# Input_channel.net
KiCad netlist of a schematic drawn in Altium Designer
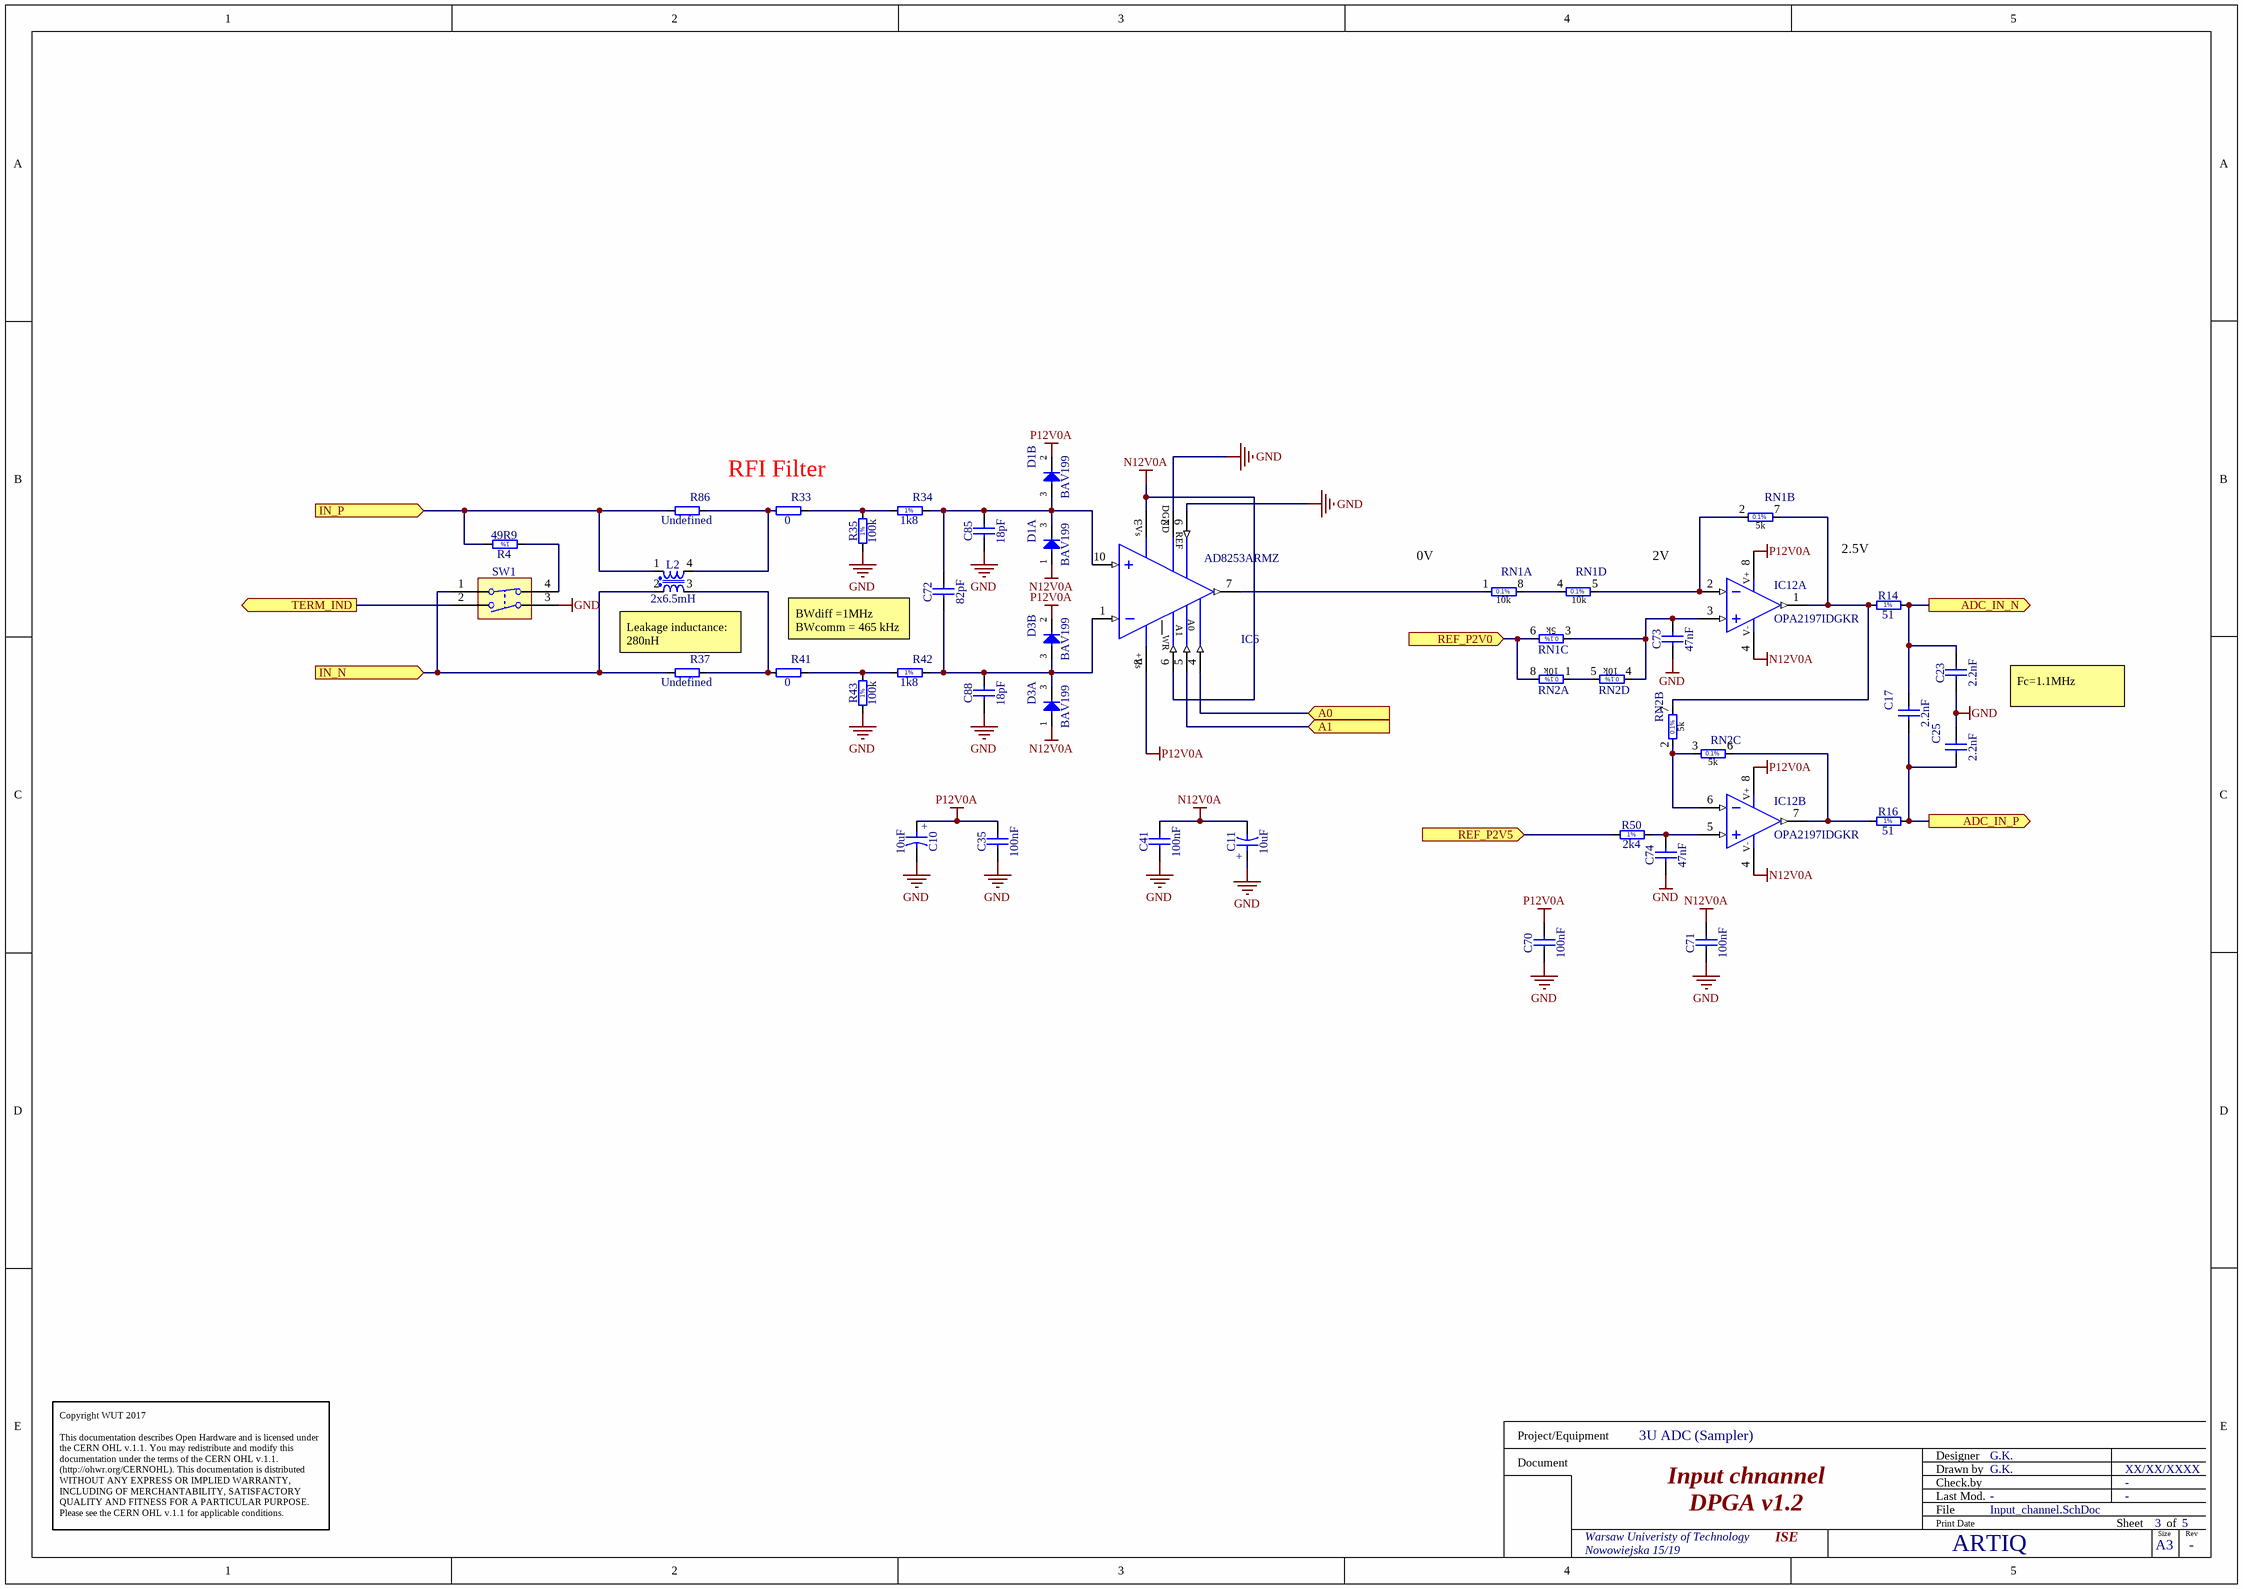
[diagram p0: Input_channel.SchDoc]

(export (version "E")
  (design (tool "Eeschema 10.0.6"))
  (components
    (comp (ref "C10")
      (value "10uF")
      (footprint "CAPMP3216X180N")
      (description "Polarised capacitor")
      (fields
        (field (name "PART NUMBER") "CTE3216-18_10UF_16V_20%_AVX_TCJ")
        (field (name "VOLTAGE") "16V")
        (field (name "AUTHOR") "CERN DEM JLC")
      )
      (libsource (lib "Capacitors") (part "Capacitor - polarized"))
    )
    (comp (ref "C11")
      (value "10uF")
      (footprint "CAPMP3216X180N")
      (description "Polarised capacitor")
      (fields
        (field (name "PART NUMBER") "CTE3216-18_10UF_16V_20%_AVX_TCJ")
        (field (name "VOLTAGE") "16V")
        (field (name "AUTHOR") "CERN DEM JLC")
      )
      (libsource (lib "Capacitors") (part "Capacitor - polarized"))
    )
    (comp (ref "C17")
      (value "2.2nF")
      (footprint "CAPC2013X100N")
      (description "Non-polarised capacitor")
      (fields
        (field (name "PART NUMBER") "CC0805_2.2NF_25V_1%_C0G")
        (field (name "VOLTAGE") "25V")
        (field (name "AUTHOR") "CERN DEM JLC")
      )
      (libsource (lib "Capacitors") (part "Capacitor - non polarized"))
    )
    (comp (ref "C23")
      (value "2.2nF")
      (footprint "CAPC2013X100N")
      (description "Non-polarised capacitor")
      (fields
        (field (name "PART NUMBER") "CC0805_2.2NF_25V_1%_C0G")
        (field (name "VOLTAGE") "25V")
        (field (name "AUTHOR") "CERN DEM JLC")
      )
      (libsource (lib "Capacitors") (part "Capacitor - non polarized"))
    )
    (comp (ref "C25")
      (value "2.2nF")
      (footprint "CAPC2013X100N")
      (description "Non-polarised capacitor")
      (fields
        (field (name "PART NUMBER") "CC0805_2.2NF_25V_1%_C0G")
        (field (name "VOLTAGE") "25V")
        (field (name "AUTHOR") "CERN DEM JLC")
      )
      (libsource (lib "Capacitors") (part "Capacitor - non polarized"))
    )
    (comp (ref "C35")
      (value "100nF")
      (footprint "CAPC1005X55N")
      (description "Non-polarised capacitor")
      (fields
        (field (name "PART NUMBER") "CC0402_100NF_16V_10%_X7R")
        (field (name "VOLTAGE") "16V")
        (field (name "AUTHOR") "CERN DEM JLC")
      )
      (libsource (lib "Capacitors") (part "Capacitor - non polarized"))
    )
    (comp (ref "C41")
      (value "100nF")
      (footprint "CAPC1005X55N")
      (description "Non-polarised capacitor")
      (fields
        (field (name "PART NUMBER") "CC0402_100NF_16V_10%_X7R")
        (field (name "VOLTAGE") "16V")
        (field (name "AUTHOR") "CERN DEM JLC")
      )
      (libsource (lib "Capacitors") (part "Capacitor - non polarized"))
    )
    (comp (ref "C70")
      (value "100nF")
      (footprint "CAPC1005X55N")
      (description "Non-polarised capacitor")
      (fields
        (field (name "PART NUMBER") "CC0402_100NF_16V_10%_X7R")
        (field (name "VOLTAGE") "16V")
        (field (name "AUTHOR") "CERN DEM JLC")
      )
      (libsource (lib "Capacitors") (part "Capacitor - non polarized"))
    )
    (comp (ref "C71")
      (value "100nF")
      (footprint "CAPC1005X55N")
      (description "Non-polarised capacitor")
      (fields
        (field (name "PART NUMBER") "CC0402_100NF_16V_10%_X7R")
        (field (name "VOLTAGE") "16V")
        (field (name "AUTHOR") "CERN DEM JLC")
      )
      (libsource (lib "Capacitors") (part "Capacitor - non polarized"))
    )
    (comp (ref "C72")
      (value "82pF")
      (footprint "CAPC2012X90N")
      (description "Non-polarised capacitor")
      (fields
        (field (name "PART NUMBER") "CC0805_82PF_100V_1%_NP0_AVX_08051A820FAT2A")
        (field (name "VOLTAGE") "100V")
        (field (name "AUTHOR") "CERN DEM WB")
      )
      (libsource (lib "Capacitors") (part "Capacitor - non polarized"))
    )
    (comp (ref "C73")
      (value "47nF")
      (footprint "CAPC2012X135N")
      (description "Non-polarised capacitor")
      (fields
        (field (name "PART NUMBER") "CC0805_47NF_25V_5%_C0G")
        (field (name "VOLTAGE") "25V")
        (field (name "AUTHOR") "CERN DEM JLC")
      )
      (libsource (lib "Capacitors") (part "Capacitor - non polarized"))
    )
    (comp (ref "C74")
      (value "47nF")
      (footprint "CAPC2012X135N")
      (description "Non-polarised capacitor")
      (fields
        (field (name "PART NUMBER") "CC0805_47NF_25V_5%_C0G")
        (field (name "VOLTAGE") "25V")
        (field (name "AUTHOR") "CERN DEM JLC")
      )
      (libsource (lib "Capacitors") (part "Capacitor - non polarized"))
    )
    (comp (ref "C85")
      (value "18pF")
      (footprint "CAPC1608X87N")
      (description "Non-polarised capacitor")
      (fields
        (field (name "PART NUMBER") "CC0603_18PF_50V_5%_NP0")
        (field (name "VOLTAGE") "50V")
        (field (name "AUTHOR") "CERN DEM JLC")
      )
      (libsource (lib "Capacitors") (part "Capacitor - non polarized"))
    )
    (comp (ref "C88")
      (value "18pF")
      (footprint "CAPC1608X87N")
      (description "Non-polarised capacitor")
      (fields
        (field (name "PART NUMBER") "CC0603_18PF_50V_5%_NP0")
        (field (name "VOLTAGE") "50V")
        (field (name "AUTHOR") "CERN DEM JLC")
      )
      (libsource (lib "Capacitors") (part "Capacitor - non polarized"))
    )
    (comp (ref "D1")
      (value "BAV199")
      (footprint "SOT95P240X110-3N")
      (description "Serial Diode")
      (fields
        (field (name "VOLTAGE") "75V")
        (field (name "POWER") "250mW")
        (field (name "AUTHOR") "CERN DEM JMW")
      )
      (libsource (lib "ICs And Semiconductors") (part "Diode x2 A1C3_A3C2"))
    )
    (comp (ref "D3")
      (value "BAV199")
      (footprint "SOT95P240X110-3N")
      (description "Serial Diode")
      (fields
        (field (name "VOLTAGE") "75V")
        (field (name "POWER") "250mW")
        (field (name "AUTHOR") "CERN DEM JMW")
      )
      (libsource (lib "ICs And Semiconductors") (part "Diode x2 A1C3_A3C2"))
    )
    (comp (ref "IC6")
      (value "AD8253ARMZ")
      (footprint "SOP50P490X110-10N")
      (description "10MHz, 20V/us, G= 1, 10, 100, 1000 iCMOS Programmable Gain Instrumentation Amplifier")
      (fields (field (name "MANUFACTURER") "ANALOG DEVICES") (field (name "AUTHOR") "CERN DEM JLC"))
      (libsource (lib "ICs And Semiconductors") (part "AD8253"))
    )
    (comp (ref "IC12")
      (value "OPA2197IDGKR")
      (footprint "SOP65P490X110-8N")
      (description "36-V, Precision, Rail-to-Rail Input Output, Low Offset Voltage Op Amp 8-VSSOP")
      (fields (field (name "MANUFACTURER") "TEXAS INSTRUMENTS") (field (name "AUTHOR") "GK"))
      (libsource (lib "LIBRARY_SCH") (part "OA_OPA2197IDGKR"))
    )
    (comp (ref "L2")
      (value "2x6.5mH")
      (footprint "IND_WURTH_WE-SL2")
      (description "Inductor Common Mode")
      (fields
        (field (name "PART NUMBER") "IND_6.5MH_50%_WURTH_WE-SL2-744229")
        (field (name "POWER") "400mA")
        (field (name "AUTHOR") "CERN DEM JLC")
      )
      (libsource (lib "Inductors & Transformers") (part "Inductor Common Mode 1Dot-4 2Dot-3"))
    )
    (comp (ref "R4")
      (value "49R9")
      (footprint "RESC3225X70N")
      (description "Resistor - 1%")
      (fields
        (field (name "PART NUMBER") "R1210_49R9_1%_0.5W_100PPM_VISHAY_CRCW")
        (field (name "POWER") "0.5W")
        (field (name "AUTHOR") "CERN DEM JMW")
      )
      (libsource (lib "Resistors") (part "Resistor - 1%"))
    )
    (comp (ref "R14")
      (value "51")
      (footprint "RESC1005X40N")
      (description "Resistor - 1%")
      (fields
        (field (name "PART NUMBER") "R0402_51R_1%_0.0625W_100PPM")
        (field (name "POWER") "0.0625W")
        (field (name "AUTHOR") "CERN DEM JLC")
      )
      (libsource (lib "Resistors") (part "Resistor - 1%"))
    )
    (comp (ref "R16")
      (value "51")
      (footprint "RESC1005X40N")
      (description "Resistor - 1%")
      (fields
        (field (name "PART NUMBER") "R0402_51R_1%_0.0625W_100PPM")
        (field (name "POWER") "0.0625W")
        (field (name "AUTHOR") "CERN DEM JLC")
      )
      (libsource (lib "Resistors") (part "Resistor - 1%"))
    )
    (comp (ref "R33")
      (value "0")
      (footprint "RESC1608X55N")
      (description "Resistor")
      (fields
        (field (name "PART NUMBER") "R0603_0R_JUMPER")
        (field (name "MANUFACTURER") "GENERIC")
        (field (name "AUTHOR") "CERN DEM JLC")
      )
      (libsource (lib "Resistors") (part "Resistor"))
    )
    (comp (ref "R34")
      (value "1k8")
      (footprint "RESC1608X55N")
      (description "Resistor - 1%")
      (fields
        (field (name "PART NUMBER") "R0603_1K8_1%_0.1W_100PPM")
        (field (name "POWER") "0.1W")
        (field (name "AUTHOR") "CERN DEM JLC")
      )
      (libsource (lib "Resistors") (part "Resistor - 1%"))
    )
    (comp (ref "R35")
      (value "100k")
      (footprint "RESC1608X55N")
      (description "Resistor - 1%")
      (fields
        (field (name "PART NUMBER") "R0603_100K_1%_0.1W_100PPM")
        (field (name "POWER") "0.1W")
        (field (name "AUTHOR") "CERN DEM JLC")
      )
      (libsource (lib "Resistors") (part "Resistor - 1%"))
    )
    (comp (ref "R37")
      (value "Undefined")
      (footprint "RESC1608X55N")
      (description "Resistor")
      (fields (field (name "PART NUMBER") "R0603_NO-VALUE") (field (name "AUTHOR") "CERN DEM JLC"))
      (libsource (lib "Resistors") (part "Resistor"))
    )
    (comp (ref "R41")
      (value "0")
      (footprint "RESC1608X55N")
      (description "Resistor")
      (fields
        (field (name "PART NUMBER") "R0603_0R_JUMPER")
        (field (name "MANUFACTURER") "GENERIC")
        (field (name "AUTHOR") "CERN DEM JLC")
      )
      (libsource (lib "Resistors") (part "Resistor"))
    )
    (comp (ref "R42")
      (value "1k8")
      (footprint "RESC1608X55N")
      (description "Resistor - 1%")
      (fields
        (field (name "PART NUMBER") "R0603_1K8_1%_0.1W_100PPM")
        (field (name "POWER") "0.1W")
        (field (name "AUTHOR") "CERN DEM JLC")
      )
      (libsource (lib "Resistors") (part "Resistor - 1%"))
    )
    (comp (ref "R43")
      (value "100k")
      (footprint "RESC1608X55N")
      (description "Resistor - 1%")
      (fields
        (field (name "PART NUMBER") "R0603_100K_1%_0.1W_100PPM")
        (field (name "POWER") "0.1W")
        (field (name "AUTHOR") "CERN DEM JLC")
      )
      (libsource (lib "Resistors") (part "Resistor - 1%"))
    )
    (comp (ref "R50")
      (value "2k4")
      (footprint "RESC1005X40N")
      (description "Resistor - 1%")
      (fields
        (field (name "PART NUMBER") "R0402_2K4_1%_0.0625W_100PPM")
        (field (name "POWER") "0.0625W")
        (field (name "AUTHOR") "CERN DEM JLC")
      )
      (libsource (lib "Resistors") (part "Resistor - 1%"))
    )
    (comp (ref "R86")
      (value "Undefined")
      (footprint "RESC1608X55N")
      (description "Resistor")
      (fields (field (name "PART NUMBER") "R0603_NO-VALUE") (field (name "AUTHOR") "CERN DEM JLC"))
      (libsource (lib "Resistors") (part "Resistor"))
    )
    (comp (ref "RN1")
      (value "10k 5K 5K 10K")
      (footprint "SOIC127P600X175-8N")
      (description "DIL8 Resistor Network 4 Resistors 10k-5k-5k-10k 0.1%")
      (fields
        (field (name "PART NUMBER") "RN_10K_5K_VISHAY_AORN2-1AT3")
        (field (name "POWER") "4x0.1W")
        (field (name "AUTHOR") "CERN DEM JLC")
      )
      (libsource (lib "Resistors") (part "RN DIL8_4xR_10k-5k-5k-10k_0.1%"))
    )
    (comp (ref "RN2")
      (value "10k 5K 5K 10K")
      (footprint "SOIC127P600X175-8N")
      (description "DIL8 Resistor Network 4 Resistors 10k-5k-5k-10k 0.1%")
      (fields
        (field (name "PART NUMBER") "RN_10K_5K_VISHAY_AORN2-1AT3")
        (field (name "POWER") "4x0.1W")
        (field (name "AUTHOR") "CERN DEM JLC")
      )
      (libsource (lib "Resistors") (part "RN DIL8_4xR_10k-5k-5k-10k_0.1%"))
    )
    (comp (ref "SW1")
      (value "Switch")
      (footprint "SW_CTS_204-121ST")
      (description "2x SPST DIP Switch 1NO + 1NF")
      (fields
        (field (name "PART NUMBER") "SW_CTS_204-121ST")
        (field (name "MANUFACTURER") "CTS")
        (field (name "AUTHOR") "CERN DEM JLC")
      )
      (libsource (lib "Eletro-mechanical") (part "SW_CTS_204-121ST"))
    )
  )
  (nets
    (net (code "1") (name "/A0") (class "Default")
      (node (ref "IC6") (pin "4") (pinfunction "A0_4") (pintype "input"))
    )
    (net (code "2") (name "/A1") (class "Default")
      (node (ref "IC6") (pin "5") (pinfunction "A1_5") (pintype "input"))
    )
    (net (code "3") (name "/ADC_IN_N") (class "Default")
      (node (ref "C17") (pin "2") (pinfunction "2_2") (pintype "passive"))
      (node (ref "C23") (pin "2") (pinfunction "2_2") (pintype "passive"))
      (node (ref "R14") (pin "2") (pinfunction "2_2") (pintype "passive"))
    )
    (net (code "4") (name "/ADC_IN_P") (class "Default")
      (node (ref "C17") (pin "1") (pinfunction "1_1") (pintype "passive"))
      (node (ref "C25") (pin "1") (pinfunction "1_1") (pintype "passive"))
      (node (ref "R16") (pin "2") (pinfunction "2_2") (pintype "passive"))
    )
    (net (code "5") (name "/IN_N") (class "Default")
      (node (ref "L2") (pin "2") (pinfunction "2_2") (pintype "passive"))
      (node (ref "R37") (pin "1") (pinfunction "1_1") (pintype "passive"))
      (node (ref "SW1") (pin "1") (pinfunction "1_1") (pintype "passive"))
    )
    (net (code "6") (name "/IN_P") (class "Default")
      (node (ref "L2") (pin "1") (pinfunction "1_1") (pintype "passive"))
      (node (ref "R4") (pin "2") (pinfunction "2_2") (pintype "passive"))
      (node (ref "R86") (pin "1") (pinfunction "1_1") (pintype "passive"))
    )
    (net (code "7") (name "/REF_P2V0") (class "Default")
      (node (ref "RN1") (pin "6") (pinfunction "6_6") (pintype "passive"))
      (node (ref "RN2") (pin "8") (pinfunction "8_8") (pintype "passive"))
    )
    (net (code "8") (name "/REF_P2V5") (class "Default")
      (node (ref "R50") (pin "1") (pinfunction "1_1") (pintype "passive"))
    )
    (net (code "9") (name "/TERM_IND") (class "Default")
      (node (ref "SW1") (pin "2") (pinfunction "2_2") (pintype "passive"))
    )
    (net (code "10") (name "GND") (class "Default")
      (node (ref "C10") (pin "2") (pinfunction "2_2") (pintype "passive"))
      (node (ref "C11") (pin "1") (pinfunction "1_1") (pintype "passive"))
      (node (ref "C23") (pin "1") (pinfunction "1_1") (pintype "passive"))
      (node (ref "C25") (pin "2") (pinfunction "2_2") (pintype "passive"))
      (node (ref "C35") (pin "1") (pinfunction "1_1") (pintype "passive"))
      (node (ref "C41") (pin "1") (pinfunction "1_1") (pintype "passive"))
      (node (ref "C70") (pin "1") (pinfunction "1_1") (pintype "passive"))
      (node (ref "C71") (pin "1") (pinfunction "1_1") (pintype "passive"))
      (node (ref "C73") (pin "1") (pinfunction "1_1") (pintype "passive"))
      (node (ref "C74") (pin "1") (pinfunction "1_1") (pintype "passive"))
      (node (ref "C85") (pin "1") (pinfunction "1_1") (pintype "passive"))
      (node (ref "C88") (pin "1") (pinfunction "1_1") (pintype "passive"))
      (node (ref "IC6") (pin "2") (pinfunction "DGND_2") (pintype "power_in"))
      (node (ref "IC6") (pin "9") (pinfunction "REF_9") (pintype "input"))
      (node (ref "R35") (pin "1") (pinfunction "1_1") (pintype "passive"))
      (node (ref "R43") (pin "1") (pinfunction "1_1") (pintype "passive"))
      (node (ref "SW1") (pin "3") (pinfunction "3_3") (pintype "passive"))
    )
    (net (code "11") (name "N12V0A") (class "Default")
      (node (ref "C11") (pin "2") (pinfunction "2_2") (pintype "passive"))
      (node (ref "C41") (pin "2") (pinfunction "2_2") (pintype "passive"))
      (node (ref "C71") (pin "2") (pinfunction "2_2") (pintype "passive"))
      (node (ref "D1") (pin "1") (pinfunction "A_1") (pintype "passive"))
      (node (ref "D3") (pin "1") (pinfunction "A_1") (pintype "passive"))
      (node (ref "IC12") (pin "4") (pinfunction "V-_4") (pintype "power_in"))
      (node (ref "IC6") (pin "3") (pinfunction "-VS_3") (pintype "power_in"))
      (node (ref "IC6") (pin "6") (pinfunction "~{WR}_6") (pintype "input"))
    )
    (net (code "12") (name "Net-(D1A-COMAC)") (class "Default")
      (node (ref "C72") (pin "2") (pinfunction "2_2") (pintype "passive"))
      (node (ref "C85") (pin "2") (pinfunction "2_2") (pintype "passive"))
      (node (ref "D1") (pin "3") (pinfunction "COMAC_3") (pintype "passive"))
      (node (ref "IC6") (pin "10") (pinfunction "+IN_10") (pintype "input"))
      (node (ref "R34") (pin "2") (pinfunction "2_2") (pintype "passive"))
    )
    (net (code "13") (name "Net-(D3A-COMAC)") (class "Default")
      (node (ref "C72") (pin "1") (pinfunction "1_1") (pintype "passive"))
      (node (ref "C88") (pin "2") (pinfunction "2_2") (pintype "passive"))
      (node (ref "D3") (pin "3") (pinfunction "COMAC_3") (pintype "passive"))
      (node (ref "IC6") (pin "1") (pinfunction "-IN_1") (pintype "input"))
      (node (ref "R42") (pin "2") (pinfunction "2_2") (pintype "passive"))
    )
    (net (code "14") (name "Net-(IC6-OUT)") (class "Default")
      (node (ref "IC6") (pin "7") (pinfunction "OUT_7") (pintype "output"))
      (node (ref "RN1") (pin "1") (pinfunction "1_1") (pintype "passive"))
    )
    (net (code "15") (name "Net-(IC12A-IN+)") (class "Default")
      (node (ref "C73") (pin "2") (pinfunction "2_2") (pintype "passive"))
      (node (ref "IC12") (pin "3") (pinfunction "IN+_3") (pintype "input"))
      (node (ref "RN1") (pin "3") (pinfunction "3_3") (pintype "passive"))
      (node (ref "RN2") (pin "4") (pinfunction "4_4") (pintype "passive"))
    )
    (net (code "16") (name "Net-(IC12A-IN-)") (class "Default")
      (node (ref "IC12") (pin "2") (pinfunction "IN-_2") (pintype "input"))
      (node (ref "RN1") (pin "2") (pinfunction "2_2") (pintype "passive"))
      (node (ref "RN1") (pin "5") (pinfunction "5_5") (pintype "passive"))
    )
    (net (code "17") (name "Net-(IC12A-OUT)") (class "Default")
      (node (ref "IC12") (pin "1") (pinfunction "OUT_1") (pintype "output"))
      (node (ref "R14") (pin "1") (pinfunction "1_1") (pintype "passive"))
      (node (ref "RN1") (pin "7") (pinfunction "7_7") (pintype "passive"))
      (node (ref "RN2") (pin "7") (pinfunction "7_7") (pintype "passive"))
    )
    (net (code "18") (name "Net-(IC12B-IN+)") (class "Default")
      (node (ref "C74") (pin "2") (pinfunction "2_2") (pintype "passive"))
      (node (ref "IC12") (pin "5") (pinfunction "IN+_5") (pintype "input"))
      (node (ref "R50") (pin "2") (pinfunction "2_2") (pintype "passive"))
    )
    (net (code "19") (name "Net-(IC12B-IN-)") (class "Default")
      (node (ref "IC12") (pin "6") (pinfunction "IN-_6") (pintype "input"))
      (node (ref "RN2") (pin "2") (pinfunction "2_2") (pintype "passive"))
      (node (ref "RN2") (pin "3") (pinfunction "3_3") (pintype "passive"))
    )
    (net (code "20") (name "Net-(IC12B-OUT)") (class "Default")
      (node (ref "IC12") (pin "7") (pinfunction "OUT_7") (pintype "output"))
      (node (ref "R16") (pin "1") (pinfunction "1_1") (pintype "passive"))
      (node (ref "RN2") (pin "6") (pinfunction "6_6") (pintype "passive"))
    )
    (net (code "21") (name "Net-(L2-Pad3)") (class "Default")
      (node (ref "L2") (pin "3") (pinfunction "3_3") (pintype "passive"))
      (node (ref "R37") (pin "2") (pinfunction "2_2") (pintype "passive"))
      (node (ref "R41") (pin "1") (pinfunction "1_1") (pintype "passive"))
    )
    (net (code "22") (name "Net-(L2-Pad4)") (class "Default")
      (node (ref "L2") (pin "4") (pinfunction "4_4") (pintype "passive"))
      (node (ref "R33") (pin "1") (pinfunction "1_1") (pintype "passive"))
      (node (ref "R86") (pin "2") (pinfunction "2_2") (pintype "passive"))
    )
    (net (code "23") (name "Net-(R4-Pad1)") (class "Default")
      (node (ref "R4") (pin "1") (pinfunction "1_1") (pintype "passive"))
      (node (ref "SW1") (pin "4") (pinfunction "4_4") (pintype "passive"))
    )
    (net (code "24") (name "Net-(R33-Pad2)") (class "Default")
      (node (ref "R33") (pin "2") (pinfunction "2_2") (pintype "passive"))
      (node (ref "R34") (pin "1") (pinfunction "1_1") (pintype "passive"))
      (node (ref "R35") (pin "2") (pinfunction "2_2") (pintype "passive"))
    )
    (net (code "25") (name "Net-(R41-Pad2)") (class "Default")
      (node (ref "R41") (pin "2") (pinfunction "2_2") (pintype "passive"))
      (node (ref "R42") (pin "1") (pinfunction "1_1") (pintype "passive"))
      (node (ref "R43") (pin "2") (pinfunction "2_2") (pintype "passive"))
    )
    (net (code "26") (name "Net-(RN1-Pad4)") (class "Default")
      (node (ref "RN1") (pin "4") (pinfunction "4_4") (pintype "passive"))
      (node (ref "RN1") (pin "8") (pinfunction "8_8") (pintype "passive"))
    )
    (net (code "27") (name "Net-(RN2-Pad1)") (class "Default")
      (node (ref "RN2") (pin "1") (pinfunction "1_1") (pintype "passive"))
      (node (ref "RN2") (pin "5") (pinfunction "5_5") (pintype "passive"))
    )
    (net (code "28") (name "P12V0A") (class "Default")
      (node (ref "C10") (pin "1") (pinfunction "1_1") (pintype "passive"))
      (node (ref "C35") (pin "2") (pinfunction "2_2") (pintype "passive"))
      (node (ref "C70") (pin "2") (pinfunction "2_2") (pintype "passive"))
      (node (ref "D1") (pin "2") (pinfunction "C_2") (pintype "passive"))
      (node (ref "D3") (pin "2") (pinfunction "C_2") (pintype "passive"))
      (node (ref "IC12") (pin "8") (pinfunction "V+_8") (pintype "power_in"))
      (node (ref "IC6") (pin "8") (pinfunction "+VS_8") (pintype "power_in"))
    )
  )
)
